# Charger_Interface.net
KiCad netlist of a schematic drawn in Altium Designer
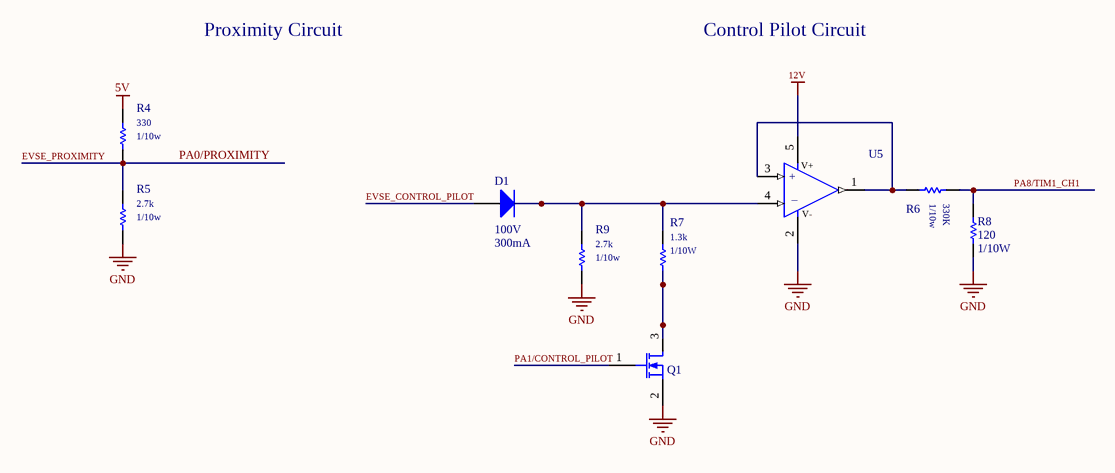
[diagram p0: Charger_Interface.SchDoc]

(export (version "E")
  (design (tool "Eeschema 10.0.6"))
  (components
    (comp (ref "D1")
      (value "DIODE GEN PURP 100V 300MA SOD123")
      (description "Diode Standard 100V 300mA (DC) Surface Mount SOD-123")
      (fields
        (field (name "MANUFACTURER") "Diodes Zetex")
        (field (name "MANUFACTURER PART NUMBER") "1N4148WQ-7-F")
      )
      (libsource (lib "Schematic Diagrams") (part "DIODE GEN PURP 100V 300MA SOD123"))
    )
    (comp (ref "Q1")
      (value "MOSFET N-CH 30V 6.2A 0.9W SOT-23")
      (footprint "MOSFET N-CH 30V 6.2A 0.9W SOT-23")
      (description "N-Channel 30V 6.2A (Ta) 900mW (Ta) Surface Mount SOT-23")
      (fields (field (name "MANUFACTURER") "Diodes") (field (name "MANUFACTURER PART NUMBER") "DMN3023L-7"))
      (libsource (lib "Schematic Diagrams") (part "MOSFET N-CH 30V 6.2A 0.9W SOT-23"))
    )
    (comp (ref "R4")
      (value "RES 330 OHM 1% 1/10W 0603")
      (footprint "RES, 0603")
      (fields
        (field (name "MANUFACTURER") "TE Connectivity")
        (field (name "MANUFACTURER PART NUMBER") "1-2176339-9")
      )
      (libsource (lib "Schematic Diagrams") (part "RES 330 OHM 1% 1/10W 0603"))
    )
    (comp (ref "R5")
      (value "RES 2.7K OHM 1% 1/10W 0603")
      (footprint "RES, 0603")
      (fields
        (field (name "MANUFACTURER") "TE Connectivity")
        (field (name "MANUFACTURER PART NUMBER") "3-2176339-0")
      )
      (libsource (lib "Schematic Diagrams") (part "RES 2.7K OHM 1% 1/10W 0603"))
    )
    (comp (ref "R6")
      (value "RES 330K OHM 1% 1/10W 0603")
      (footprint "RES, 0603")
      (description "330 kOhms ±1% 0.1W, 1/10W Chip Resistor 0603 (1608 Metric) Moisture Resistant Thick Film")
      (fields
        (field (name "MANUFACTURER") "Yageo Phycomp")
        (field (name "MANUFACTURER PART NUMBER") "RC0603FR-07330KL")
      )
      (libsource (lib "Schematic Diagrams") (part "RES 330K OHM 1% 1/10W 0603"))
    )
    (comp (ref "R7")
      (value "RES 1.3K OHM 1% 1/10W 0603")
      (footprint "RES, 0603")
      (description "1.3 kOhms ±1% 0.1W, 1/10W Chip Resistor 0603 (1608 Metric) Moisture Resistant Thick Film")
      (fields
        (field (name "MANUFACTURER") "Yageo")
        (field (name "MANUFACTURER PART NUMBER") "RC0603FR-071K3L")
      )
      (libsource (lib "Schematic Diagrams") (part "RES 1.3K OHM 1% 1/10W 0603"))
    )
    (comp (ref "R8")
      (value "RES 120 OHM 1% 1/10W 0603")
      (footprint "RES, 0603")
      (description "RES SMD 120 OHM 1% 1/10W 0603")
      (fields
        (field (name "TOLERANCE") "±1%")
        (field (name "RESISTANCE") "120")
        (field (name "POWER") "1/10W")
      )
      (libsource (lib "Schematic Diagrams") (part "RES 120 OHM 1% 1/10W 0603"))
    )
    (comp (ref "R9")
      (value "RES 2.7K OHM 1% 1/10W 0603")
      (footprint "RES, 0603")
      (fields
        (field (name "MANUFACTURER") "TE Connectivity")
        (field (name "MANUFACTURER PART NUMBER") "3-2176339-0")
      )
      (libsource (lib "Schematic Diagrams") (part "RES 2.7K OHM 1% 1/10W 0603"))
    )
    (comp (ref "U5")
      (value "IC OP AMP PREC RRIO 36V SOT23-5")
      (fields
        (field (name "MANUFACTURER") "Texas Instruments")
        (field (name "MANUFACTURER PART NUMBER") "OPA197IDBVT")
      )
      (libsource (lib "Schematic Diagrams") (part "IC OP AMP PREC RRIO 36V SOT23-5"))
    )
  )
  (nets
    (net (code "1") (name "/EVSE_CONTROL_PILOT") (class "Default")
      (node (ref "D1") (pin "1") (pinfunction "A_1") (pintype "passive"))
    )
    (net (code "2") (name "/EVSE_PROXIMITY") (class "Default")
      (node (ref "R4") (pin "2") (pinfunction "2_2") (pintype "passive"))
      (node (ref "R5") (pin "1") (pinfunction "1_1") (pintype "passive"))
    )
    (net (code "3") (name "/PA1{slash}CONTROL_PILOT") (class "Default")
      (node (ref "Q1") (pin "1") (pinfunction "G_1") (pintype "passive"))
    )
    (net (code "4") (name "/PA8{slash}TIM1_CH1") (class "Default")
      (node (ref "R6") (pin "1") (pinfunction "1_1") (pintype "passive"))
      (node (ref "R8") (pin "1") (pinfunction "1_1") (pintype "passive"))
    )
    (net (code "5") (name "5V") (class "Default")
      (node (ref "R4") (pin "1") (pinfunction "1_1") (pintype "passive"))
    )
    (net (code "6") (name "12V") (class "Default")
      (node (ref "U5") (pin "5") (pinfunction "V+_5") (pintype "power_in"))
    )
    (net (code "7") (name "GND") (class "Default")
      (node (ref "Q1") (pin "2") (pinfunction "S_2") (pintype "passive"))
      (node (ref "R5") (pin "2") (pinfunction "2_2") (pintype "passive"))
      (node (ref "R8") (pin "2") (pinfunction "2_2") (pintype "passive"))
      (node (ref "R9") (pin "2") (pinfunction "2_2") (pintype "passive"))
      (node (ref "U5") (pin "2") (pinfunction "V-_2") (pintype "power_in"))
    )
    (net (code "8") (name "Net-(D1-K)") (class "Default")
      (node (ref "D1") (pin "2") (pinfunction "K_2") (pintype "passive"))
      (node (ref "R9") (pin "1") (pinfunction "1_1") (pintype "passive"))
      (node (ref "U5") (pin "4") (pinfunction "-IN_4") (pintype "input"))
    )
    (net (code "9") (name "Net-(Q1-D)") (class "Default")
      (node (ref "Q1") (pin "3") (pinfunction "D_3") (pintype "passive"))
      (node (ref "R7") (pin "2") (pinfunction "2_2") (pintype "passive"))
    )
    (net (code "10") (name "Net-(U5-+IN)") (class "Default")
      (node (ref "R6") (pin "2") (pinfunction "2_2") (pintype "passive"))
      (node (ref "U5") (pin "1") (pinfunction "OUT_1") (pintype "output"))
      (node (ref "U5") (pin "3") (pinfunction "+IN_3") (pintype "input"))
    )
    (net (code "11") (name "unconnected-(R7-Pad2)") (class "Default")
      (node (ref "R7") (pin "2") (pinfunction "2_2") (pintype "passive"))
    )
  )
)
